# H08R61.net
KiCad netlist of a schematic drawn in EAGLE
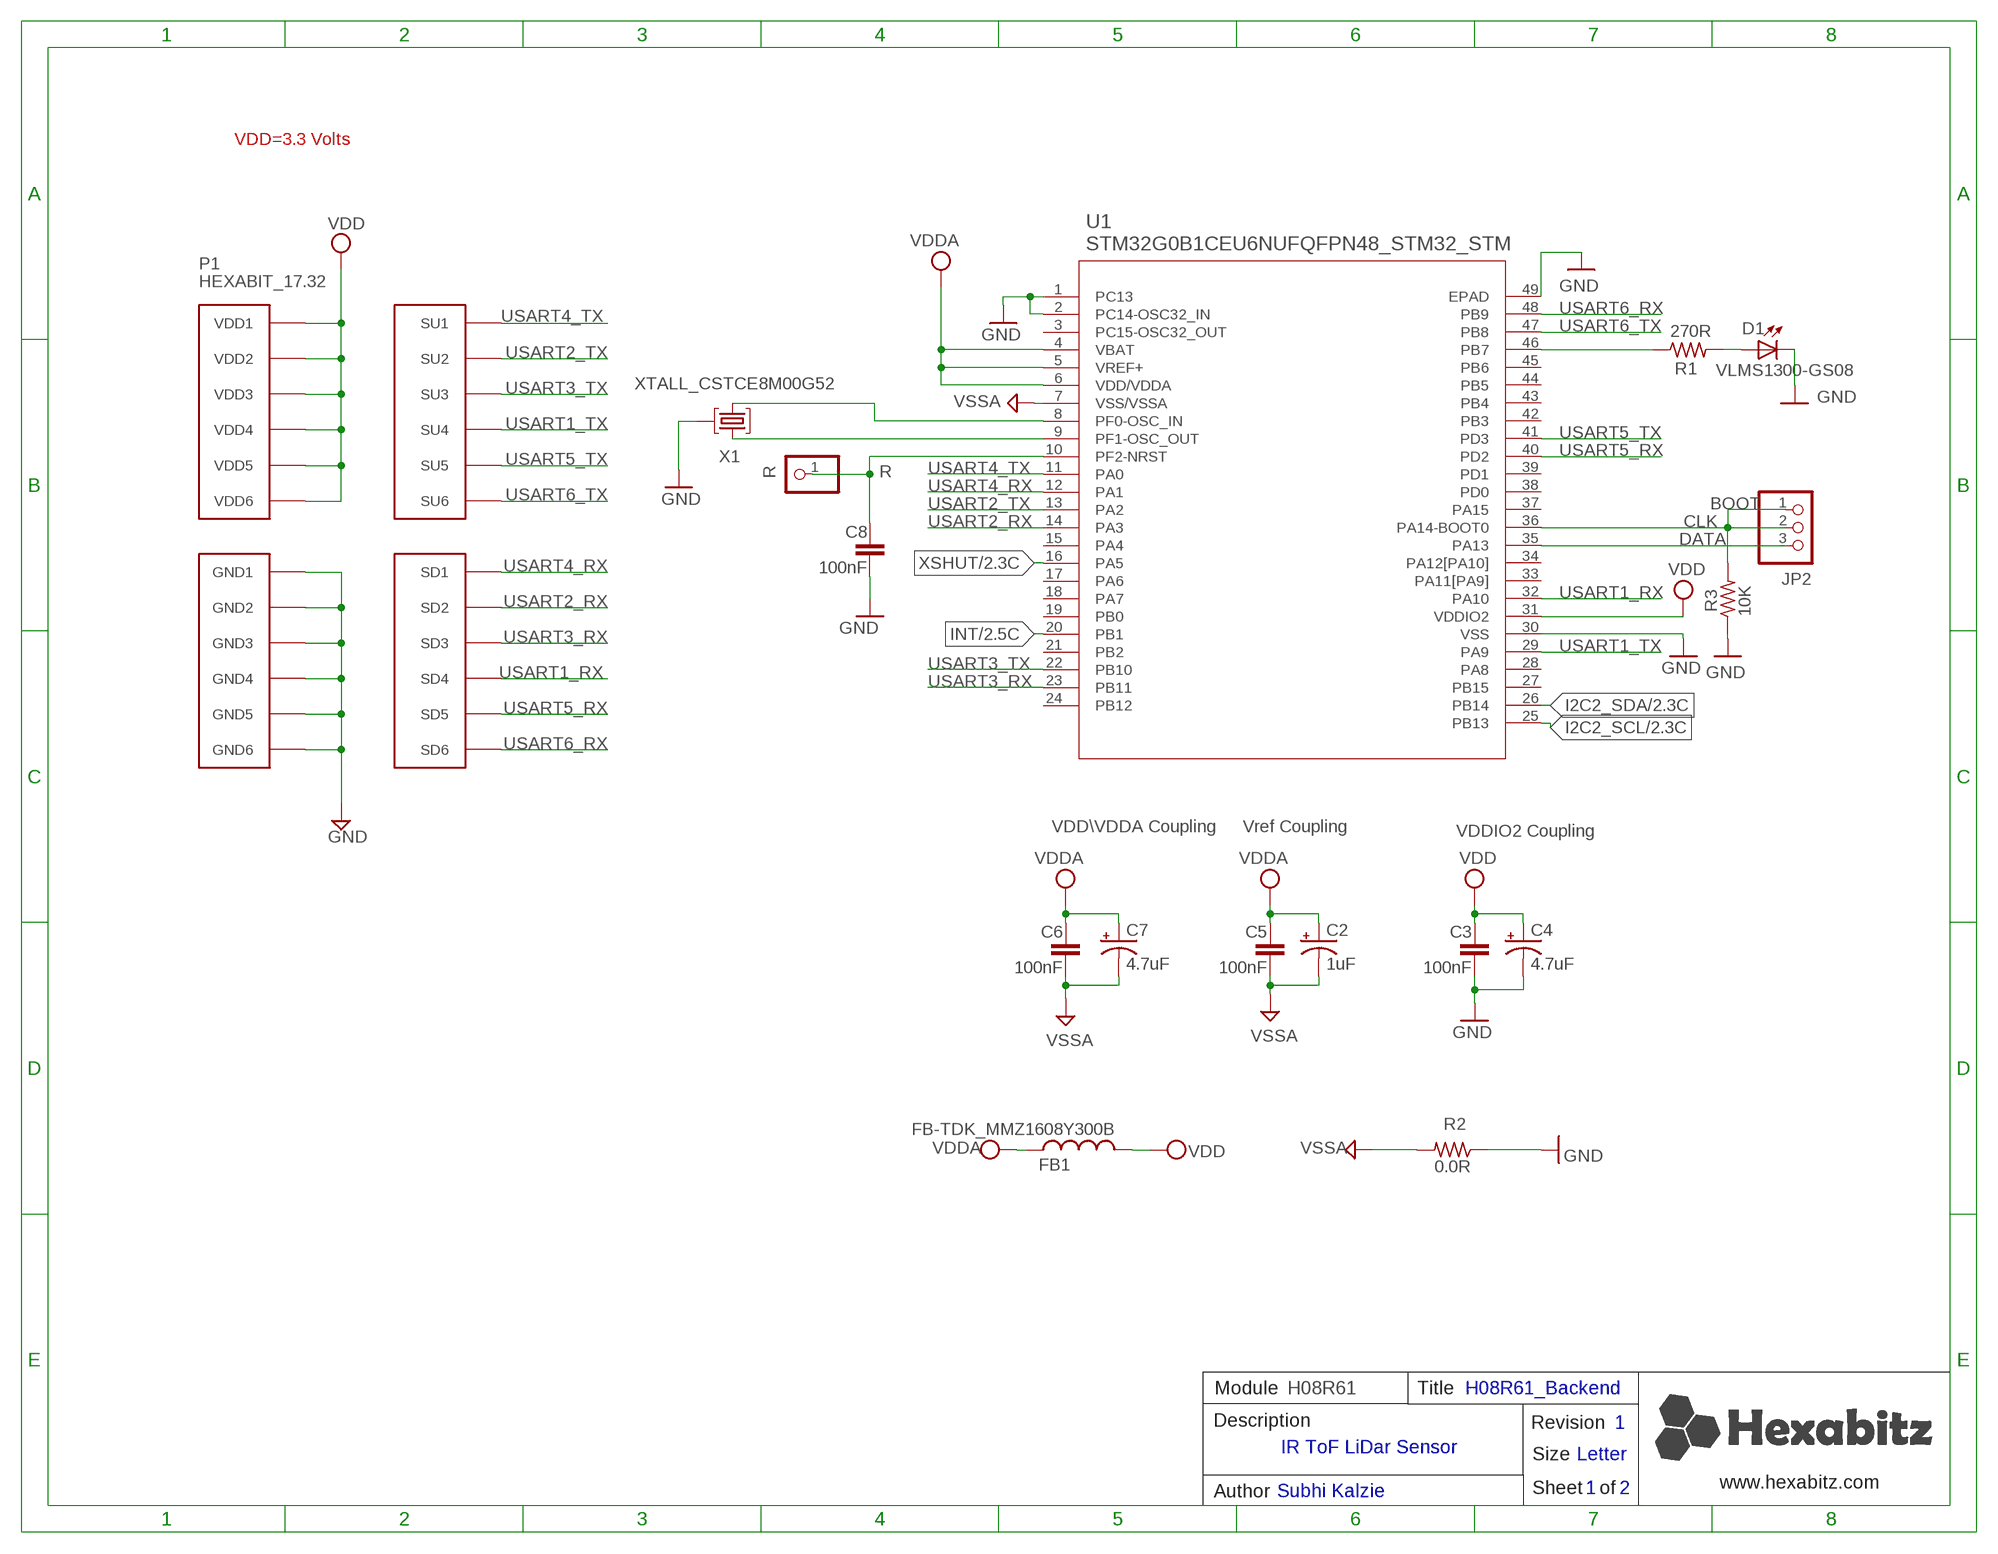
[diagram p0: schematic, sheet 1]
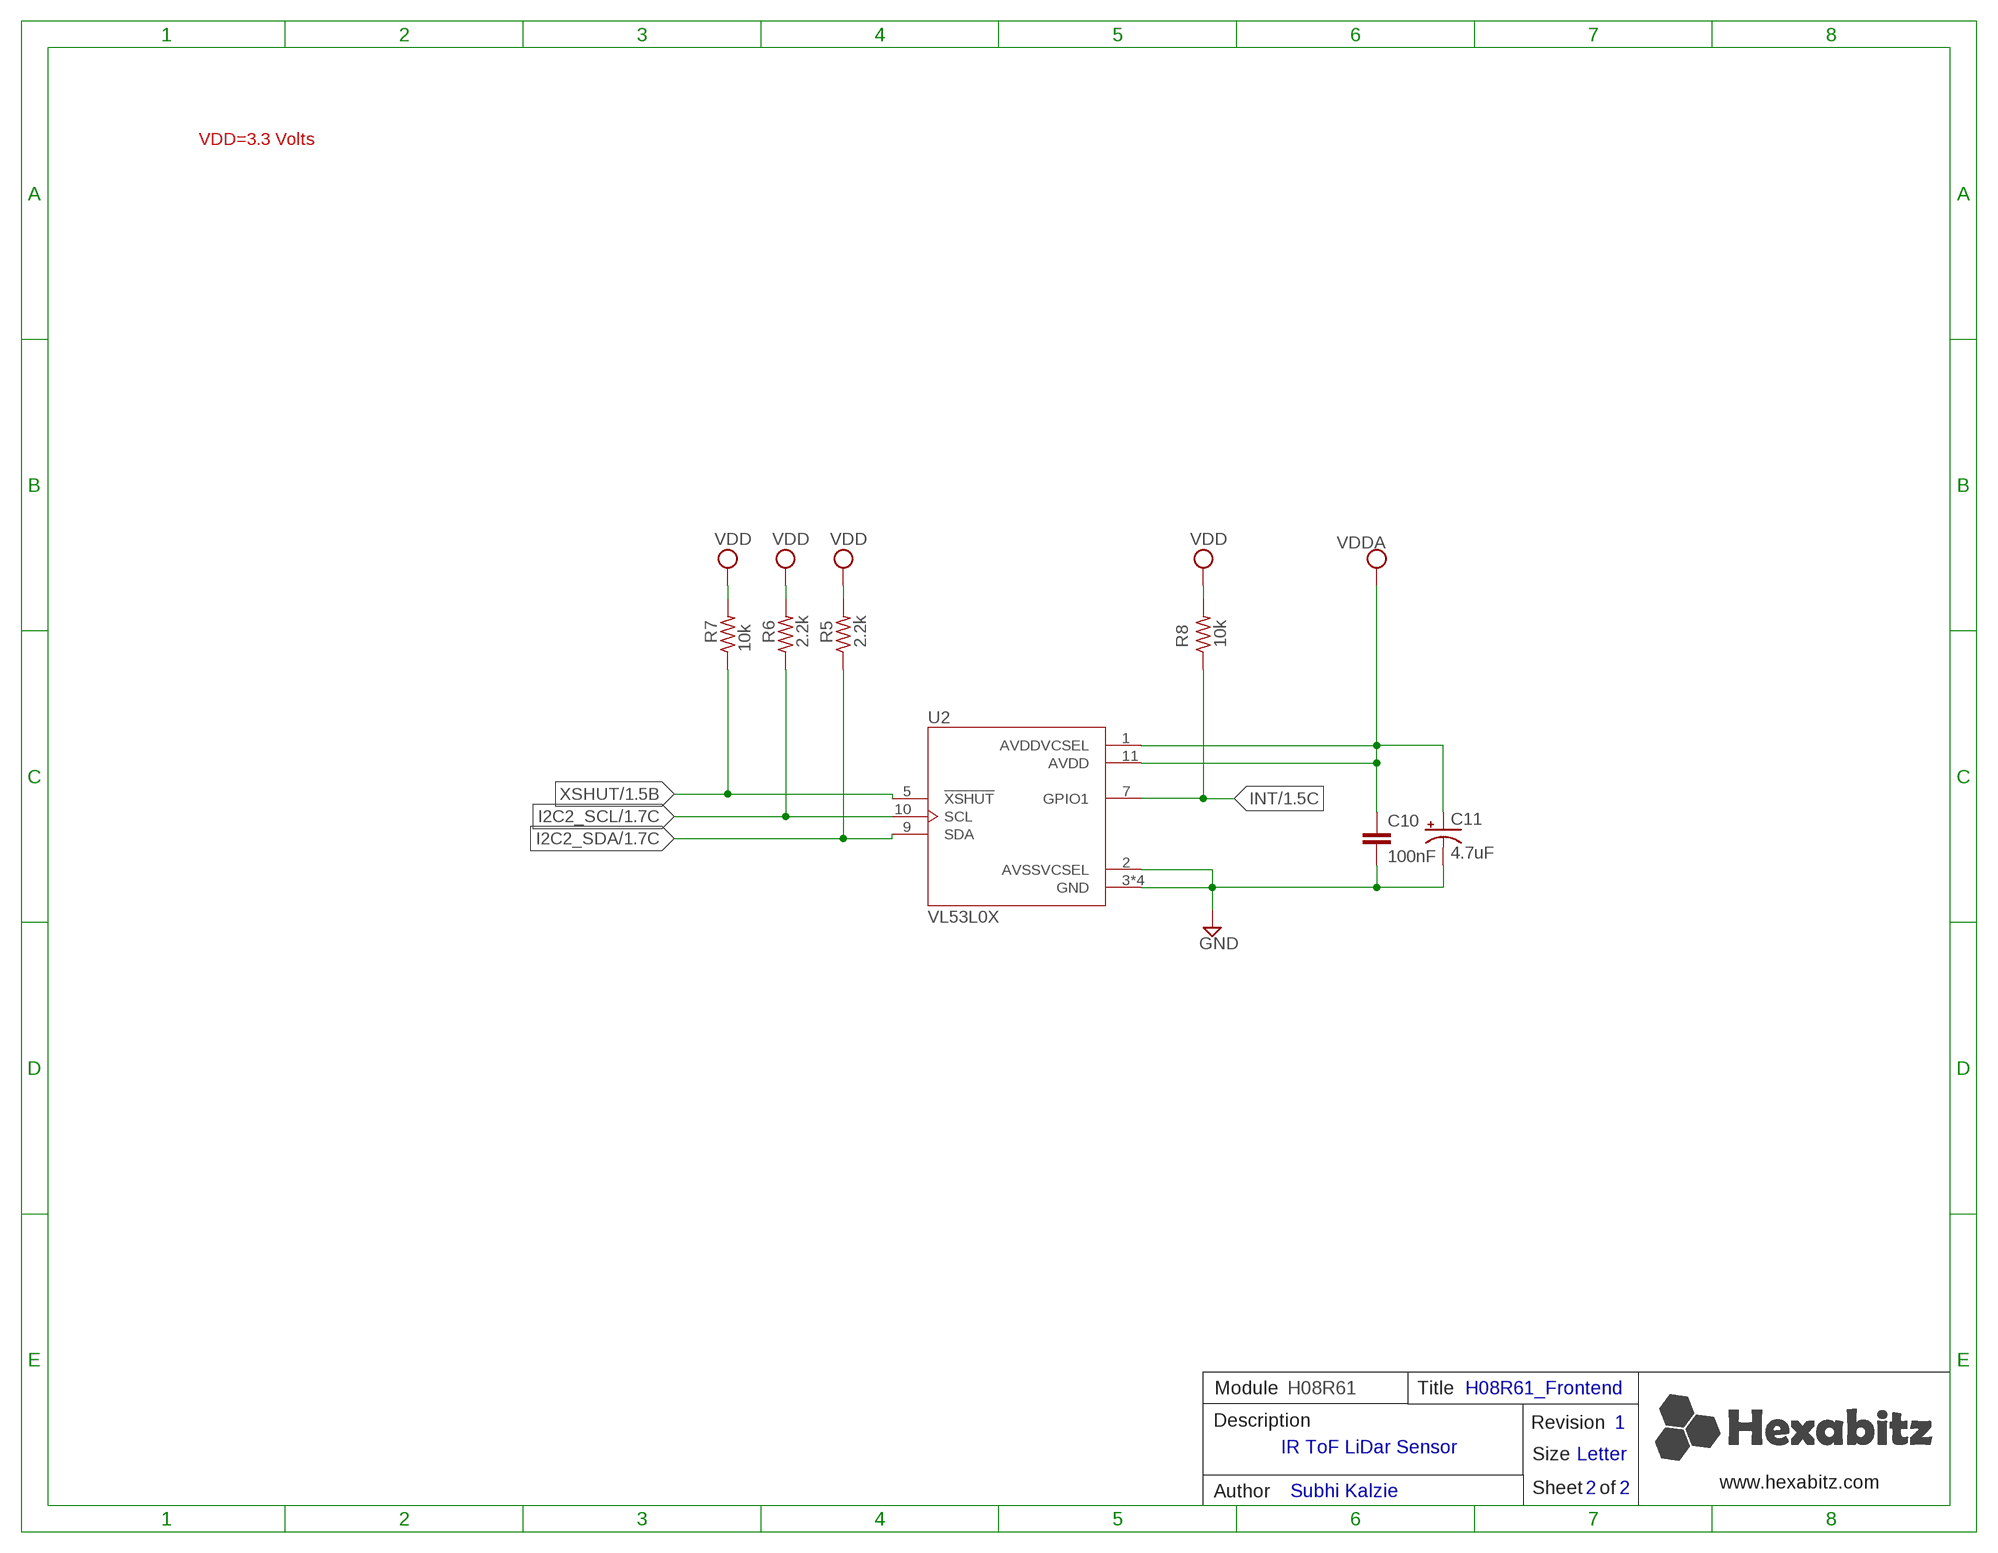
[diagram p1: schematic, sheet 2]

(export (version "E")
  (design (tool "Eeschema 10.0.6"))
  (components
    (comp (ref "C2")
      (value "1uF")
      (footprint "eagle-import:C-0805-POL")
      (libsource (lib "eagle-import") (part "C-0805-POL"))
    )
    (comp (ref "C3")
      (value "100nF")
      (footprint "eagle-import:C-0603")
      (libsource (lib "eagle-import") (part "C-0603"))
    )
    (comp (ref "C4")
      (value "4.7uF")
      (footprint "eagle-import:C-0805-POL")
      (libsource (lib "eagle-import") (part "C-0805-POL"))
    )
    (comp (ref "C5")
      (value "100nF")
      (footprint "eagle-import:C-0603")
      (libsource (lib "eagle-import") (part "C-0603"))
    )
    (comp (ref "C6")
      (value "100nF")
      (footprint "eagle-import:C-0603")
      (libsource (lib "eagle-import") (part "C-0603"))
    )
    (comp (ref "C7")
      (value "4.7uF")
      (footprint "eagle-import:C-0805-POL")
      (libsource (lib "eagle-import") (part "C-0805-POL"))
    )
    (comp (ref "C8")
      (value "100nF")
      (footprint "eagle-import:C-0603")
      (libsource (lib "eagle-import") (part "C-0603"))
    )
    (comp (ref "D1")
      (value "VLMS1300-GS08")
      (footprint "eagle-import:VLMS1300-GS08")
      (fields
        (field (name "MFN") "Vishay")
        (field (name "MPN") "VLMS1300-GS08")
        (field (name "OCTOPART_URL") "https://octopart.com/vlms1300-gs08-vishay-21709201?r=sp&s=_gcP4_q8T1SC6PJQPTQ9yA")
      )
      (libsource (lib "eagle-import") (part "VLMS1300-GS08"))
    )
    (comp (ref "FB1")
      (value "FB-TDK_MMZ1608Y300B")
      (footprint "eagle-import:FB-TDK_MMZ1608Y300B")
      (fields
        (field (name "MFN") "TDK ")
        (field (name "MPN") "MMZ1608Y300B")
        (field (name "OCTOPART_URL") "https://octopart.com/mmz1608y300b-tdk-368280?r=sp&s=cd9_2ZEqQ9q9UNBuQgHAiA")
      )
      (libsource (lib "eagle-import") (part "FB-TDK_MMZ1608Y300B"))
    )
    (comp (ref "JP2")
      (value "PINHD-1X3")
      (footprint "eagle-import:1X03")
      (libsource (lib "eagle-import") (part "PINHD-1X3"))
    )
    (comp (ref "P1")
      (value "HEXABIT_17.32")
      (footprint "eagle-import:HEXABIT_17.32")
      (libsource (lib "eagle-import") (part "HEXABIT_?17.32"))
    )
    (comp (ref "R")
      (value "R")
      (footprint "eagle-import:1X01")
      (fields (field (name "MPN") "87227-1"))
      (libsource (lib "eagle-import") (part "PINHD-1X1"))
    )
    (comp (ref "R1")
      (value "270R")
      (footprint "eagle-import:R-0603")
      (libsource (lib "eagle-import") (part "R-0603"))
    )
    (comp (ref "R2")
      (value "0.0R")
      (footprint "eagle-import:R-0603")
      (fields
        (field (name "MFN") "Yageo")
        (field (name "MPN") "RC0603JR-070RL")
        (field (name "OCTOPART_URL") "https://octopart.com/rc0603jr-070rl-yageo-1241539?r=sp&s=X2NteqRjRNWrnx42Y0aliA")
        (field (name "RESISTANCE") "0.0 Ohm")
      )
      (libsource (lib "eagle-import") (part "HEXABITZ_RCLS_33906182_R-0603"))
    )
    (comp (ref "R3")
      (value "10K")
      (footprint "eagle-import:R-0603")
      (libsource (lib "eagle-import") (part "R-0603"))
    )
    (comp (ref "U1")
      (value "STM32G0B1CEU6NUFQFPN48_STM32_STM")
      (footprint "eagle-import:UFQFPN48_STM32_STM")
      (fields
        (field (name "MPN") "STM32G0B1CEU6N")
        (field (name "COPYRIGHT") "Copyright (C) 2022 Ultra Librarian. All rights reserved.")
      )
      (libsource (lib "eagle-import") (part "STM32G0B1CEU6NUFQFPN48_STM32_STM"))
    )
    (comp (ref "X1")
      (value "XTALL_CSTCE8M00G52")
      (footprint "eagle-import:XTALL_CSTCE8M00G52")
      (fields (field (name "MPN") "CSTCE8M00G52Z-R0"))
      (libsource (lib "eagle-import") (part "XTALL_CSTCE8M00G52"))
    )
    (comp (ref "C10")
      (value "100nF")
      (footprint "eagle-import:C-0603")
      (libsource (lib "eagle-import") (part "C-0603"))
    )
    (comp (ref "C11")
      (value "4.7uF")
      (footprint "eagle-import:C-0805-POL")
      (libsource (lib "eagle-import") (part "C-0805-POL"))
    )
    (comp (ref "R5")
      (value "2.2k")
      (footprint "eagle-import:R-0603")
      (libsource (lib "eagle-import") (part "R-0603"))
    )
    (comp (ref "R6")
      (value "2.2k")
      (footprint "eagle-import:R-0603")
      (libsource (lib "eagle-import") (part "R-0603"))
    )
    (comp (ref "R7")
      (value "10k")
      (footprint "eagle-import:R-0603")
      (libsource (lib "eagle-import") (part "R-0603"))
    )
    (comp (ref "R8")
      (value "10k")
      (footprint "eagle-import:R-0603")
      (libsource (lib "eagle-import") (part "R-0603"))
    )
    (comp (ref "U2")
      (value "VL53L0X")
      (footprint "eagle-import:SENSOR_VL53L0X")
      (fields (field (name "MPN") "VL53L0CXV0DH/1"))
      (libsource (lib "eagle-import") (part "VL53L0X"))
    )
  )
  (nets
    (net (code "1") (name "CLK") (class "Default")
      (node (ref "JP2") (pin "1") (pinfunction "1_1") (pintype "passive"))
      (node (ref "JP2") (pin "2") (pinfunction "2_2") (pintype "passive"))
      (node (ref "R3") (pin "2") (pinfunction "2_2") (pintype "passive"))
      (node (ref "U1") (pin "36") (pinfunction "PA14-BOOT0_36") (pintype "bidirectional"))
    )
    (net (code "2") (name "DATA") (class "Default")
      (node (ref "JP2") (pin "3") (pinfunction "3_3") (pintype "passive"))
      (node (ref "U1") (pin "35") (pinfunction "PA13_35") (pintype "bidirectional"))
    )
    (net (code "3") (name "GND") (class "Default")
      (node (ref "C10") (pin "2") (pinfunction "2_2") (pintype "passive"))
      (node (ref "C11") (pin "2") (pinfunction "-_2") (pintype "passive"))
      (node (ref "C3") (pin "2") (pinfunction "2_2") (pintype "passive"))
      (node (ref "C4") (pin "2") (pinfunction "-_2") (pintype "passive"))
      (node (ref "C8") (pin "2") (pinfunction "2_2") (pintype "passive"))
      (node (ref "D1") (pin "C") (pinfunction "C_C") (pintype "passive"))
      (node (ref "P1") (pin "PAD_PD10") (pinfunction "GND4_PAD_PD10") (pintype "power_in"))
      (node (ref "P1") (pin "PAD_PD11") (pinfunction "GND5_PAD_PD11") (pintype "power_in"))
      (node (ref "P1") (pin "PAD_PD12") (pinfunction "GND6_PAD_PD12") (pintype "power_in"))
      (node (ref "P1") (pin "PAD_PD7") (pinfunction "GND1_PAD_PD7") (pintype "power_in"))
      (node (ref "P1") (pin "PAD_PD8") (pinfunction "GND2_PAD_PD8") (pintype "power_in"))
      (node (ref "P1") (pin "PAD_PD9") (pinfunction "GND3_PAD_PD9") (pintype "power_in"))
      (node (ref "R2") (pin "1") (pinfunction "1_1") (pintype "passive"))
      (node (ref "R3") (pin "1") (pinfunction "1_1") (pintype "passive"))
      (node (ref "U1") (pin "1") (pinfunction "PC13_1") (pintype "bidirectional"))
      (node (ref "U1") (pin "2") (pinfunction "PC14-OSC32_IN_2") (pintype "bidirectional"))
      (node (ref "U1") (pin "30") (pinfunction "VSS_30") (pintype "passive"))
      (node (ref "U1") (pin "49") (pinfunction "EPAD_49") (pintype "passive"))
      (node (ref "U2") (pin "12") (pinfunction "GND_12") (pintype "power_in"))
      (node (ref "U2") (pin "2") (pinfunction "AVSSVCSEL_2") (pintype "power_in"))
      (node (ref "U2") (pin "3") (pinfunction "GND_3") (pintype "power_in"))
      (node (ref "U2") (pin "4") (pinfunction "GND_4") (pintype "power_in"))
      (node (ref "U2") (pin "6") (pinfunction "GND_6") (pintype "power_in"))
      (node (ref "X1") (pin "P$2") (pinfunction "2_P$2") (pintype "passive"))
    )
    (net (code "4") (name "I2C2_SCL") (class "Default")
      (node (ref "R6") (pin "1") (pinfunction "1_1") (pintype "passive"))
      (node (ref "U1") (pin "25") (pinfunction "PB13_25") (pintype "bidirectional"))
      (node (ref "U2") (pin "10") (pinfunction "SCL_10") (pintype "input"))
    )
    (net (code "5") (name "I2C2_SDA") (class "Default")
      (node (ref "R5") (pin "1") (pinfunction "1_1") (pintype "passive"))
      (node (ref "U1") (pin "26") (pinfunction "PB14_26") (pintype "bidirectional"))
      (node (ref "U2") (pin "9") (pinfunction "SDA_9") (pintype "bidirectional"))
    )
    (net (code "6") (name "INT") (class "Default")
      (node (ref "R8") (pin "1") (pinfunction "1_1") (pintype "passive"))
      (node (ref "U1") (pin "20") (pinfunction "PB1_20") (pintype "bidirectional"))
      (node (ref "U2") (pin "7") (pinfunction "GPIO1_7") (pintype "output"))
    )
    (net (code "7") (name "Net-(D1-PadA)") (class "Default")
      (node (ref "D1") (pin "A") (pinfunction "A_A") (pintype "passive"))
      (node (ref "R1") (pin "2") (pinfunction "2_2") (pintype "passive"))
    )
    (net (code "8") (name "Net-(U1-PB7)") (class "Default")
      (node (ref "R1") (pin "1") (pinfunction "1_1") (pintype "passive"))
      (node (ref "U1") (pin "46") (pinfunction "PB7_46") (pintype "bidirectional"))
    )
    (net (code "9") (name "Net-(U1-PF0-OSC_IN)") (class "Default")
      (node (ref "U1") (pin "8") (pinfunction "PF0-OSC_IN_8") (pintype "bidirectional"))
      (node (ref "X1") (pin "P$3") (pinfunction "3_P$3") (pintype "passive"))
    )
    (net (code "10") (name "Net-(U1-PF1-OSC_OUT)") (class "Default")
      (node (ref "U1") (pin "9") (pinfunction "PF1-OSC_OUT_9") (pintype "bidirectional"))
      (node (ref "X1") (pin "P$1") (pinfunction "1_P$1") (pintype "passive"))
    )
    (net (code "11") (name "Net-(U1-PF2-NRST)") (class "Default")
      (node (ref "C8") (pin "1") (pinfunction "1_1") (pintype "passive"))
      (node (ref "R") (pin "1") (pinfunction "1_1") (pintype "passive"))
      (node (ref "U1") (pin "10") (pinfunction "PF2-NRST_10") (pintype "bidirectional"))
    )
    (net (code "12") (name "USART1_RX") (class "Default")
      (node (ref "P1") (pin "PAD_PD4") (pinfunction "SD4_PAD_PD4") (pintype "bidirectional"))
      (node (ref "U1") (pin "32") (pinfunction "PA10_32") (pintype "bidirectional"))
    )
    (net (code "13") (name "USART1_TX") (class "Default")
      (node (ref "P1") (pin "PAD_PU4") (pinfunction "SU4_PAD_PU4") (pintype "bidirectional"))
      (node (ref "U1") (pin "29") (pinfunction "PA9_29") (pintype "bidirectional"))
    )
    (net (code "14") (name "USART2_RX") (class "Default")
      (node (ref "P1") (pin "PAD_PD2") (pinfunction "SD2_PAD_PD2") (pintype "bidirectional"))
      (node (ref "U1") (pin "14") (pinfunction "PA3_14") (pintype "bidirectional"))
    )
    (net (code "15") (name "USART2_TX") (class "Default")
      (node (ref "P1") (pin "PAD_PU2") (pinfunction "SU2_PAD_PU2") (pintype "bidirectional"))
      (node (ref "U1") (pin "13") (pinfunction "PA2_13") (pintype "bidirectional"))
    )
    (net (code "16") (name "USART3_RX") (class "Default")
      (node (ref "P1") (pin "PAD_PD3") (pinfunction "SD3_PAD_PD3") (pintype "bidirectional"))
      (node (ref "U1") (pin "23") (pinfunction "PB11_23") (pintype "bidirectional"))
    )
    (net (code "17") (name "USART3_TX") (class "Default")
      (node (ref "P1") (pin "PAD_PU3") (pinfunction "SU3_PAD_PU3") (pintype "bidirectional"))
      (node (ref "U1") (pin "22") (pinfunction "PB10_22") (pintype "bidirectional"))
    )
    (net (code "18") (name "USART4_RX") (class "Default")
      (node (ref "P1") (pin "PAD_PD1") (pinfunction "SD1_PAD_PD1") (pintype "bidirectional"))
      (node (ref "U1") (pin "12") (pinfunction "PA1_12") (pintype "bidirectional"))
    )
    (net (code "19") (name "USART4_TX") (class "Default")
      (node (ref "P1") (pin "PAD_PU1") (pinfunction "SU1_PAD_PU1") (pintype "bidirectional"))
      (node (ref "U1") (pin "11") (pinfunction "PA0_11") (pintype "bidirectional"))
    )
    (net (code "20") (name "USART5_RX") (class "Default")
      (node (ref "P1") (pin "PAD_PD5") (pinfunction "SD5_PAD_PD5") (pintype "bidirectional"))
      (node (ref "U1") (pin "40") (pinfunction "PD2_40") (pintype "bidirectional"))
    )
    (net (code "21") (name "USART5_TX") (class "Default")
      (node (ref "P1") (pin "PAD_PU5") (pinfunction "SU5_PAD_PU5") (pintype "bidirectional"))
      (node (ref "U1") (pin "41") (pinfunction "PD3_41") (pintype "bidirectional"))
    )
    (net (code "22") (name "USART6_RX") (class "Default")
      (node (ref "P1") (pin "PAD_PD6") (pinfunction "SD6_PAD_PD6") (pintype "bidirectional"))
      (node (ref "U1") (pin "48") (pinfunction "PB9_48") (pintype "bidirectional"))
    )
    (net (code "23") (name "USART6_TX") (class "Default")
      (node (ref "P1") (pin "PAD_PU6") (pinfunction "SU6_PAD_PU6") (pintype "bidirectional"))
      (node (ref "U1") (pin "47") (pinfunction "PB8_47") (pintype "bidirectional"))
    )
    (net (code "24") (name "VDD") (class "Default")
      (node (ref "C3") (pin "1") (pinfunction "1_1") (pintype "passive"))
      (node (ref "C4") (pin "1") (pinfunction "+_1") (pintype "passive"))
      (node (ref "FB1") (pin "2") (pinfunction "2_2") (pintype "passive"))
      (node (ref "P1") (pin "PAD_PU10") (pinfunction "VDD4_PAD_PU10") (pintype "power_in"))
      (node (ref "P1") (pin "PAD_PU11") (pinfunction "VDD5_PAD_PU11") (pintype "power_in"))
      (node (ref "P1") (pin "PAD_PU12") (pinfunction "VDD6_PAD_PU12") (pintype "power_in"))
      (node (ref "P1") (pin "PAD_PU7") (pinfunction "VDD1_PAD_PU7") (pintype "power_in"))
      (node (ref "P1") (pin "PAD_PU8") (pinfunction "VDD2_PAD_PU8") (pintype "power_in"))
      (node (ref "P1") (pin "PAD_PU9") (pinfunction "VDD3_PAD_PU9") (pintype "power_in"))
      (node (ref "R5") (pin "2") (pinfunction "2_2") (pintype "passive"))
      (node (ref "R6") (pin "2") (pinfunction "2_2") (pintype "passive"))
      (node (ref "R7") (pin "2") (pinfunction "2_2") (pintype "passive"))
      (node (ref "R8") (pin "2") (pinfunction "2_2") (pintype "passive"))
      (node (ref "U1") (pin "31") (pinfunction "VDDIO2_31") (pintype "power_in"))
    )
    (net (code "25") (name "VDDA") (class "Default")
      (node (ref "C10") (pin "1") (pinfunction "1_1") (pintype "passive"))
      (node (ref "C11") (pin "1") (pinfunction "+_1") (pintype "passive"))
      (node (ref "C2") (pin "1") (pinfunction "+_1") (pintype "passive"))
      (node (ref "C5") (pin "1") (pinfunction "1_1") (pintype "passive"))
      (node (ref "C6") (pin "1") (pinfunction "1_1") (pintype "passive"))
      (node (ref "C7") (pin "1") (pinfunction "+_1") (pintype "passive"))
      (node (ref "FB1") (pin "1") (pinfunction "1_1") (pintype "passive"))
      (node (ref "U1") (pin "4") (pinfunction "VBAT_4") (pintype "power_in"))
      (node (ref "U1") (pin "5") (pinfunction "VREF+_5") (pintype "power_in"))
      (node (ref "U1") (pin "6") (pinfunction "VDD/VDDA_6") (pintype "power_in"))
      (node (ref "U2") (pin "1") (pinfunction "AVDDVCSEL_1") (pintype "power_in"))
      (node (ref "U2") (pin "11") (pinfunction "AVDD_11") (pintype "power_in"))
    )
    (net (code "26") (name "VSSA") (class "Default")
      (node (ref "C2") (pin "2") (pinfunction "-_2") (pintype "passive"))
      (node (ref "C5") (pin "2") (pinfunction "2_2") (pintype "passive"))
      (node (ref "C6") (pin "2") (pinfunction "2_2") (pintype "passive"))
      (node (ref "C7") (pin "2") (pinfunction "-_2") (pintype "passive"))
      (node (ref "R2") (pin "2") (pinfunction "2_2") (pintype "passive"))
      (node (ref "U1") (pin "7") (pinfunction "VSS/VSSA_7") (pintype "passive"))
    )
    (net (code "27") (name "XSHUT") (class "Default")
      (node (ref "R7") (pin "1") (pinfunction "1_1") (pintype "passive"))
      (node (ref "U1") (pin "16") (pinfunction "PA5_16") (pintype "bidirectional"))
      (node (ref "U2") (pin "5") (pinfunction "~{XSHUT}_5") (pintype "input"))
    )
    (net (code "28") (name "unconnected-(U1-PA4-Pad15)") (class "Default")
      (node (ref "U1") (pin "15") (pinfunction "PA4_15") (pintype "bidirectional"))
    )
    (net (code "29") (name "unconnected-(U1-PA6-Pad17)") (class "Default")
      (node (ref "U1") (pin "17") (pinfunction "PA6_17") (pintype "bidirectional"))
    )
    (net (code "30") (name "unconnected-(U1-PA7-Pad18)") (class "Default")
      (node (ref "U1") (pin "18") (pinfunction "PA7_18") (pintype "bidirectional"))
    )
    (net (code "31") (name "unconnected-(U1-PA8-Pad28)") (class "Default")
      (node (ref "U1") (pin "28") (pinfunction "PA8_28") (pintype "bidirectional"))
    )
    (net (code "32") (name "unconnected-(U1-PA11[PA9]-Pad33)") (class "Default")
      (node (ref "U1") (pin "33") (pinfunction "PA11[PA9]_33") (pintype "bidirectional"))
    )
    (net (code "33") (name "unconnected-(U1-PA12[PA10]-Pad34)") (class "Default")
      (node (ref "U1") (pin "34") (pinfunction "PA12[PA10]_34") (pintype "bidirectional"))
    )
    (net (code "34") (name "unconnected-(U1-PA15-Pad37)") (class "Default")
      (node (ref "U1") (pin "37") (pinfunction "PA15_37") (pintype "bidirectional"))
    )
    (net (code "35") (name "unconnected-(U1-PB0-Pad19)") (class "Default")
      (node (ref "U1") (pin "19") (pinfunction "PB0_19") (pintype "bidirectional"))
    )
    (net (code "36") (name "unconnected-(U1-PB2-Pad21)") (class "Default")
      (node (ref "U1") (pin "21") (pinfunction "PB2_21") (pintype "bidirectional"))
    )
    (net (code "37") (name "unconnected-(U1-PB3-Pad42)") (class "Default")
      (node (ref "U1") (pin "42") (pinfunction "PB3_42") (pintype "bidirectional"))
    )
    (net (code "38") (name "unconnected-(U1-PB4-Pad43)") (class "Default")
      (node (ref "U1") (pin "43") (pinfunction "PB4_43") (pintype "bidirectional"))
    )
    (net (code "39") (name "unconnected-(U1-PB5-Pad44)") (class "Default")
      (node (ref "U1") (pin "44") (pinfunction "PB5_44") (pintype "bidirectional"))
    )
    (net (code "40") (name "unconnected-(U1-PB6-Pad45)") (class "Default")
      (node (ref "U1") (pin "45") (pinfunction "PB6_45") (pintype "bidirectional"))
    )
    (net (code "41") (name "unconnected-(U1-PB12-Pad24)") (class "Default")
      (node (ref "U1") (pin "24") (pinfunction "PB12_24") (pintype "bidirectional"))
    )
    (net (code "42") (name "unconnected-(U1-PB15-Pad27)") (class "Default")
      (node (ref "U1") (pin "27") (pinfunction "PB15_27") (pintype "bidirectional"))
    )
    (net (code "43") (name "unconnected-(U1-PC15-OSC32_OUT-Pad3)") (class "Default")
      (node (ref "U1") (pin "3") (pinfunction "PC15-OSC32_OUT_3") (pintype "bidirectional"))
    )
    (net (code "44") (name "unconnected-(U1-PD0-Pad38)") (class "Default")
      (node (ref "U1") (pin "38") (pinfunction "PD0_38") (pintype "bidirectional"))
    )
    (net (code "45") (name "unconnected-(U1-PD1-Pad39)") (class "Default")
      (node (ref "U1") (pin "39") (pinfunction "PD1_39") (pintype "bidirectional"))
    )
  )
)
